# AD717-2.net
KiCad netlist of a schematic drawn in Altium Designer
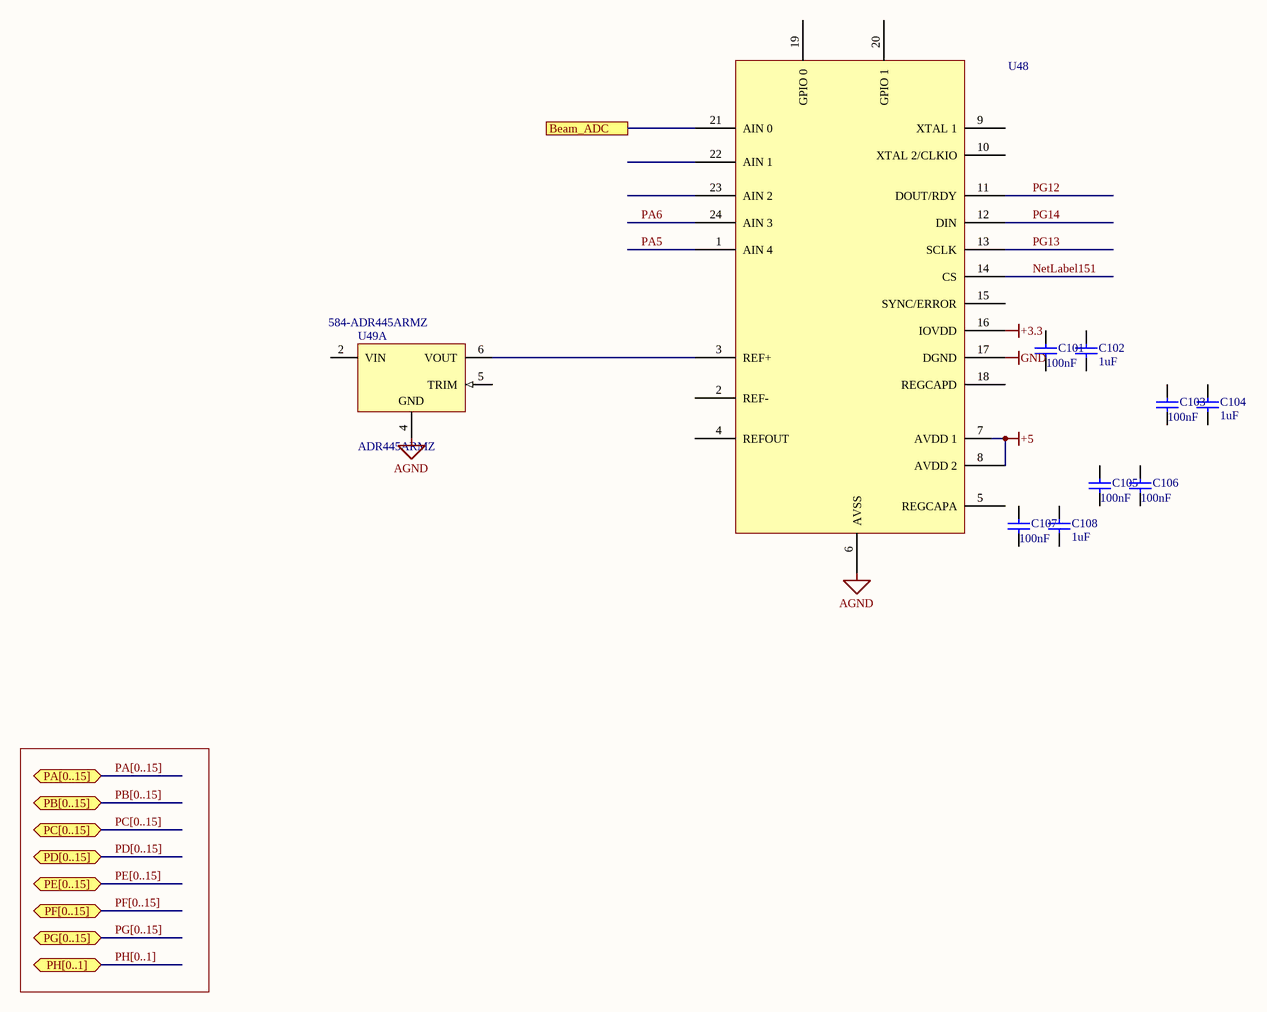
[diagram p0: AD717-2.SchDoc]

(export (version "E")
  (design (tool "Eeschema 10.0.6"))
  (components
    (comp (ref "C101")
      (value "Capacitor")
      (footprint "C0402")
      (description "CAP CER 0.1UF 16V X7R 0402")
      (fields
        (field (name "MANUFACTURER") "Yageo")
        (field (name "MANUFACTURER PART NUMBER") "CC0402KRX7R7BB104")
        (field (name "CAPACITANCE") "100nF")
      )
      (libsource (lib "MCD_PARTS_database") (part "Capacitor"))
    )
    (comp (ref "C102")
      (value "1uF")
      (footprint "C0603")
      (description "Capacitor, MLCC, 1uF, 6V3, X5R, 10%, 0603, T=0,8mm")
      (fields
        (field (name "INTERNAL_PART_NUMBER") "MCD-00238")
        (field (name "MANUFACTURER_PART_NUMBER") "CC0603KRX5R5BB105")
        (field (name "PROVIDED_BY") "SUBCO")
      )
      (libsource (lib "MCD_PARTS_database") (part "Capacitor"))
    )
    (comp (ref "C103")
      (value "Capacitor")
      (footprint "C0402")
      (description "CAP CER 0.1UF 16V X7R 0402")
      (fields
        (field (name "MANUFACTURER") "Yageo")
        (field (name "MANUFACTURER PART NUMBER") "CC0402KRX7R7BB104")
        (field (name "CAPACITANCE") "100nF")
      )
      (libsource (lib "MCD_PARTS_database") (part "Capacitor"))
    )
    (comp (ref "C104")
      (value "1uF")
      (footprint "C0603")
      (description "Capacitor, MLCC, 1uF, 6V3, X5R, 10%, 0603, T=0,8mm")
      (fields
        (field (name "INTERNAL_PART_NUMBER") "MCD-00238")
        (field (name "MANUFACTURER_PART_NUMBER") "CC0603KRX5R5BB105")
        (field (name "PROVIDED_BY") "SUBCO")
      )
      (libsource (lib "MCD_PARTS_database") (part "Capacitor"))
    )
    (comp (ref "C105")
      (value "Capacitor")
      (footprint "C0402")
      (description "CAP CER 0.1UF 16V X7R 0402")
      (fields
        (field (name "MANUFACTURER") "Yageo")
        (field (name "MANUFACTURER PART NUMBER") "CC0402KRX7R7BB104")
        (field (name "CAPACITANCE") "100nF")
      )
      (libsource (lib "MCD_PARTS_database") (part "Capacitor"))
    )
    (comp (ref "C106")
      (value "Capacitor")
      (footprint "C0402")
      (description "CAP CER 0.1UF 16V X7R 0402")
      (fields
        (field (name "MANUFACTURER") "Yageo")
        (field (name "MANUFACTURER PART NUMBER") "CC0402KRX7R7BB104")
        (field (name "CAPACITANCE") "100nF")
      )
      (libsource (lib "MCD_PARTS_database") (part "Capacitor"))
    )
    (comp (ref "C107")
      (value "Capacitor")
      (footprint "C0402")
      (description "CAP CER 0.1UF 16V X7R 0402")
      (fields
        (field (name "MANUFACTURER") "Yageo")
        (field (name "MANUFACTURER PART NUMBER") "CC0402KRX7R7BB104")
        (field (name "CAPACITANCE") "100nF")
      )
      (libsource (lib "MCD_PARTS_database") (part "Capacitor"))
    )
    (comp (ref "C108")
      (value "1uF")
      (footprint "C0603")
      (description "Capacitor, MLCC, 1uF, 6V3, X5R, 10%, 0603, T=0,8mm")
      (fields
        (field (name "INTERNAL_PART_NUMBER") "MCD-00238")
        (field (name "MANUFACTURER_PART_NUMBER") "CC0603KRX5R5BB105")
        (field (name "PROVIDED_BY") "SUBCO")
      )
      (libsource (lib "MCD_PARTS_database") (part "Capacitor"))
    )
    (comp (ref "U48")
      (value "AD7177-2")
      (footprint "AD7177-2BRUZ")
      (libsource (lib "ZLS_Schematic_lib") (part "AD7177-2"))
    )
    (comp (ref "U49")
      (value "ADR445ARMZ")
      (footprint "ADI-RM-8_M")
      (fields
        (field (name "MANUFACTURER") "Analog Devices")
        (field (name "SUPPLIER PART NUMBER 1") "584-ADR445ARMZ")
        (field (name "TOLERANCE") "0.12%")
      )
      (libsource (lib "Altium Content Vault") (part "ADI-ADR4XX-8"))
    )
  )
  (nets
    (net (code "110") (name "+3.3") (class "Default")
      (node (ref "U48") (pin "16") (pinfunction "IOVDD_16") (pintype "passive"))
    )
    (net (code "111") (name "+5") (class "Default")
      (node (ref "U48") (pin "7") (pinfunction "AVDD_1_7") (pintype "passive"))
      (node (ref "U48") (pin "8") (pinfunction "AVDD_2_8") (pintype "passive"))
    )
    (net (code "112") (name "/Beam_ADC") (class "Default")
      (node (ref "U48") (pin "21") (pinfunction "AIN_0_21") (pintype "passive"))
    )
    (net (code "113") (name "/NetLabel151") (class "Default")
      (node (ref "U48") (pin "14") (pinfunction "CS_14") (pintype "passive"))
    )
    (net (code "114") (name "/PA5") (class "Default")
      (node (ref "U48") (pin "1") (pinfunction "AIN_4_1") (pintype "passive"))
    )
    (net (code "115") (name "/PA6") (class "Default")
      (node (ref "U48") (pin "24") (pinfunction "AIN_3_24") (pintype "passive"))
    )
    (net (code "122") (name "/PG12") (class "Default")
      (node (ref "U48") (pin "11") (pinfunction "DOUT/RDY_11") (pintype "passive"))
    )
    (net (code "123") (name "/PG13") (class "Default")
      (node (ref "U48") (pin "13") (pinfunction "SCLK_13") (pintype "passive"))
    )
    (net (code "124") (name "/PG14") (class "Default")
      (node (ref "U48") (pin "12") (pinfunction "DIN_12") (pintype "passive"))
    )
    (net (code "127") (name "AGND") (class "Default")
      (node (ref "U48") (pin "6") (pinfunction "AVSS_6") (pintype "passive"))
      (node (ref "U49") (pin "4") (pinfunction "GND_4") (pintype "power_in"))
    )
    (net (code "128") (name "GND") (class "Default")
      (node (ref "U48") (pin "17") (pinfunction "DGND_17") (pintype "passive"))
    )
    (net (code "129") (name "Net-(U48-REF+)") (class "Default")
      (node (ref "U48") (pin "3") (pinfunction "REF+_3") (pintype "passive"))
      (node (ref "U49") (pin "6") (pinfunction "VOUT_6") (pintype "power_in"))
    )
    (net (code "130") (name "unconnected-(C101-Pad1)") (class "Default")
      (node (ref "C101") (pin "1") (pinfunction "1_1") (pintype "passive"))
    )
    (net (code "131") (name "unconnected-(C101-Pad2)") (class "Default")
      (node (ref "C101") (pin "2") (pinfunction "2_2") (pintype "passive"))
    )
    (net (code "132") (name "unconnected-(C102-Pad1)") (class "Default")
      (node (ref "C102") (pin "1") (pinfunction "1_1") (pintype "passive"))
    )
    (net (code "133") (name "unconnected-(C102-Pad2)") (class "Default")
      (node (ref "C102") (pin "2") (pinfunction "2_2") (pintype "passive"))
    )
    (net (code "134") (name "unconnected-(C103-Pad1)") (class "Default")
      (node (ref "C103") (pin "1") (pinfunction "1_1") (pintype "passive"))
    )
    (net (code "135") (name "unconnected-(C103-Pad2)") (class "Default")
      (node (ref "C103") (pin "2") (pinfunction "2_2") (pintype "passive"))
    )
    (net (code "136") (name "unconnected-(C104-Pad1)") (class "Default")
      (node (ref "C104") (pin "1") (pinfunction "1_1") (pintype "passive"))
    )
    (net (code "137") (name "unconnected-(C104-Pad2)") (class "Default")
      (node (ref "C104") (pin "2") (pinfunction "2_2") (pintype "passive"))
    )
    (net (code "138") (name "unconnected-(C105-Pad1)") (class "Default")
      (node (ref "C105") (pin "1") (pinfunction "1_1") (pintype "passive"))
    )
    (net (code "139") (name "unconnected-(C105-Pad2)") (class "Default")
      (node (ref "C105") (pin "2") (pinfunction "2_2") (pintype "passive"))
    )
    (net (code "140") (name "unconnected-(C106-Pad1)") (class "Default")
      (node (ref "C106") (pin "1") (pinfunction "1_1") (pintype "passive"))
    )
    (net (code "141") (name "unconnected-(C106-Pad2)") (class "Default")
      (node (ref "C106") (pin "2") (pinfunction "2_2") (pintype "passive"))
    )
    (net (code "142") (name "unconnected-(C107-Pad1)") (class "Default")
      (node (ref "C107") (pin "1") (pinfunction "1_1") (pintype "passive"))
    )
    (net (code "143") (name "unconnected-(C107-Pad2)") (class "Default")
      (node (ref "C107") (pin "2") (pinfunction "2_2") (pintype "passive"))
    )
    (net (code "144") (name "unconnected-(C108-Pad1)") (class "Default")
      (node (ref "C108") (pin "1") (pinfunction "1_1") (pintype "passive"))
    )
    (net (code "145") (name "unconnected-(C108-Pad2)") (class "Default")
      (node (ref "C108") (pin "2") (pinfunction "2_2") (pintype "passive"))
    )
    (net (code "146") (name "unconnected-(U48-AIN_1-Pad22)") (class "Default")
      (node (ref "U48") (pin "22") (pinfunction "AIN_1_22") (pintype "passive"))
    )
    (net (code "147") (name "unconnected-(U48-AIN_2-Pad23)") (class "Default")
      (node (ref "U48") (pin "23") (pinfunction "AIN_2_23") (pintype "passive"))
    )
    (net (code "148") (name "unconnected-(U48-GPIO_0-Pad19)") (class "Default")
      (node (ref "U48") (pin "19") (pinfunction "GPIO_0_19") (pintype "passive"))
    )
    (net (code "149") (name "unconnected-(U48-GPIO_1-Pad20)") (class "Default")
      (node (ref "U48") (pin "20") (pinfunction "GPIO_1_20") (pintype "passive"))
    )
    (net (code "150") (name "unconnected-(U48-REF--Pad2)") (class "Default")
      (node (ref "U48") (pin "2") (pinfunction "REF-_2") (pintype "passive"))
    )
    (net (code "151") (name "unconnected-(U48-REFOUT-Pad4)") (class "Default")
      (node (ref "U48") (pin "4") (pinfunction "REFOUT_4") (pintype "passive"))
    )
    (net (code "152") (name "unconnected-(U48-REGCAPA-Pad5)") (class "Default")
      (node (ref "U48") (pin "5") (pinfunction "REGCAPA_5") (pintype "passive"))
    )
    (net (code "153") (name "unconnected-(U48-REGCAPD-Pad18)") (class "Default")
      (node (ref "U48") (pin "18") (pinfunction "REGCAPD_18") (pintype "passive"))
    )
    (net (code "154") (name "unconnected-(U48-SYNC{slash}ERROR-Pad15)") (class "Default")
      (node (ref "U48") (pin "15") (pinfunction "SYNC/ERROR_15") (pintype "passive"))
    )
    (net (code "155") (name "unconnected-(U48-XTAL_1-Pad9)") (class "Default")
      (node (ref "U48") (pin "9") (pinfunction "XTAL_1_9") (pintype "passive"))
    )
    (net (code "156") (name "unconnected-(U48-XTAL_2{slash}CLKIO-Pad10)") (class "Default")
      (node (ref "U48") (pin "10") (pinfunction "XTAL_2/CLKIO_10") (pintype "passive"))
    )
    (net (code "157") (name "unconnected-(U49A-TRIM-Pad5)") (class "Default")
      (node (ref "U49") (pin "5") (pinfunction "TRIM_5") (pintype "input"))
    )
    (net (code "158") (name "unconnected-(U49A-VIN-Pad2)") (class "Default")
      (node (ref "U49") (pin "2") (pinfunction "VIN_2") (pintype "power_in"))
    )
  )
)
